# CPU.net
KiCad netlist of a schematic drawn in Altium Designer
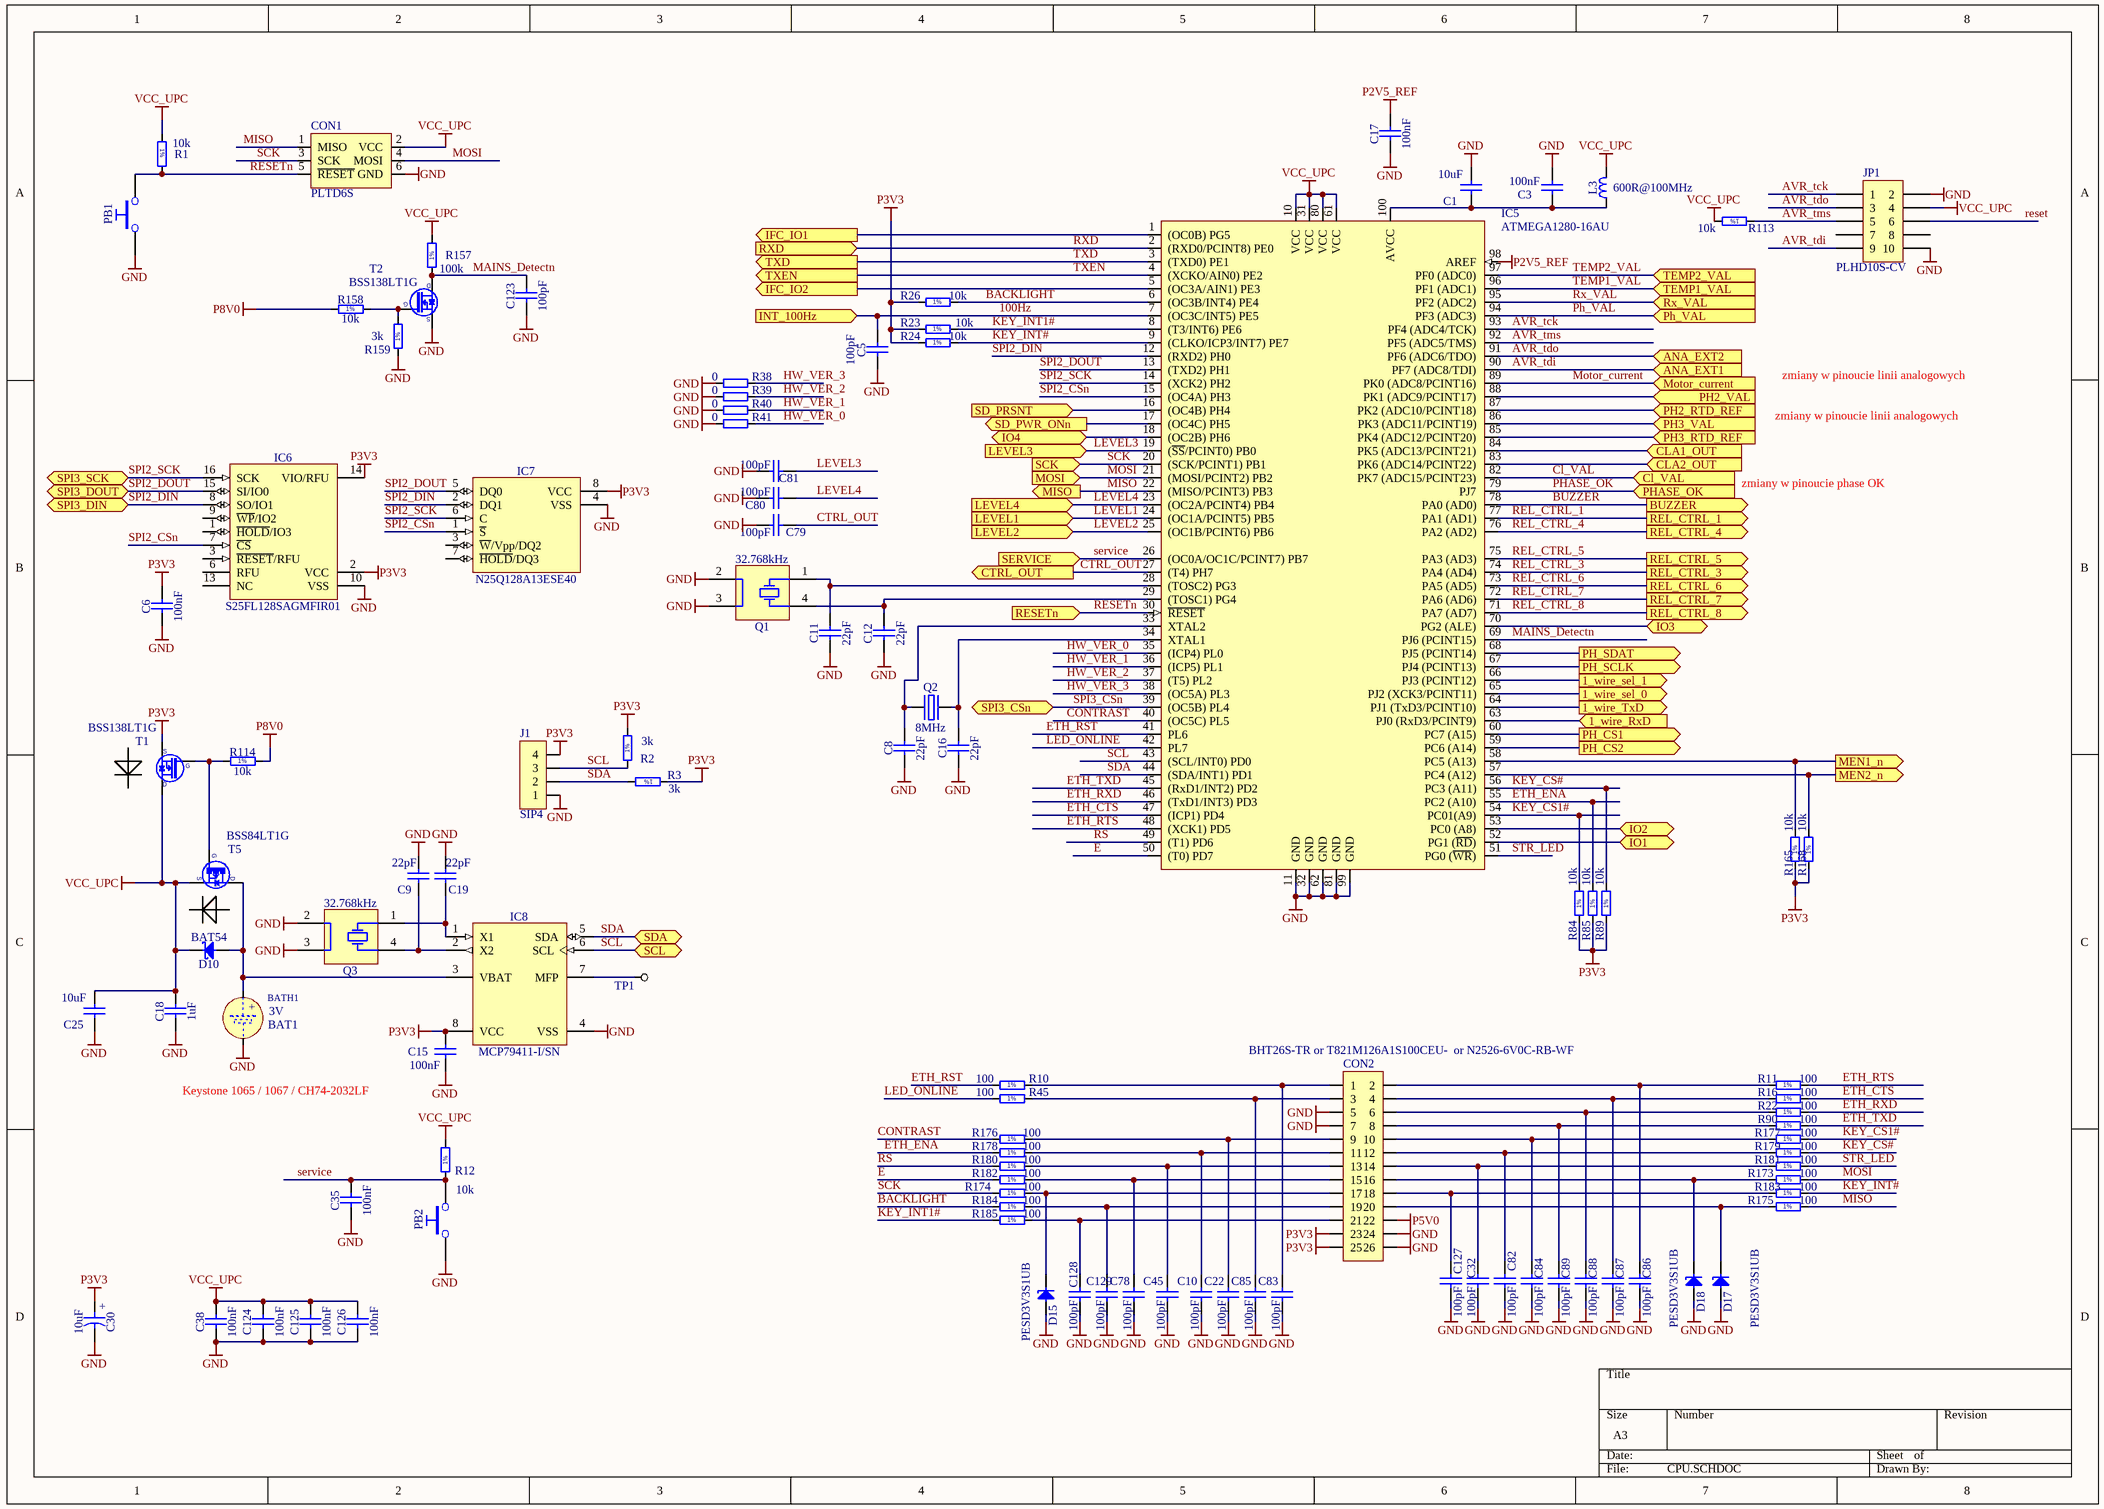
[diagram p0: CPU.SCHDOC]

(export (version "E")
  (design (tool "Eeschema 10.0.6"))
  (components
    (comp (ref "BAT1")
      (value "3V")
      (footprint "BAT_VARTA_CR2032")
      (description "Battery for use only with Socket Holder")
      (fields
        (field (name "PART NUMBER") "BAT_VARTA_CR2032")
        (field (name "POWER") "230mAh")
        (field (name "AUTHOR") "CERN DEM JLC")
      )
      (libsource (lib "Eletro-mechanical") (part "Battery No Pin"))
    )
    (comp (ref "BATH1")
      (value "~")
      (footprint "BATH_KEYSTONE_1065_rev")
      (description "Battery Holder whit 2 Pin")
      (fields
        (field (name "PART NUMBER") "BATH_KEYSTONE_1065")
        (field (name "MANUFACTURER") "KEYSTONE")
        (field (name "AUTHOR") "CERN DEM MR")
      )
      (libsource (lib "LIBRARY_SCH") (part "BATTERY_HOLD_2012"))
    )
    (comp (ref "C1")
      (value "10uF")
      (footprint "CAPC2012X135N")
      (description "Non-polarised capacitor")
      (fields
        (field (name "PART NUMBER") "CC0805_10UF_16V_10%_X5R")
        (field (name "VOLTAGE") "16V")
        (field (name "AUTHOR") "CERN DEM JLC")
      )
      (libsource (lib "Capacitors") (part "Capacitor - non polarized"))
    )
    (comp (ref "C3")
      (value "100nF")
      (footprint "CAPC1608X87N")
      (description "Non-polarised capacitor")
      (fields
        (field (name "PART NUMBER") "CC0603_100NF_50V_10%_X7R")
        (field (name "VOLTAGE") "50V")
        (field (name "AUTHOR") "CERN DEM JLC")
      )
      (libsource (lib "Capacitors") (part "Capacitor - non polarized"))
    )
    (comp (ref "C5")
      (value "100pF")
      (footprint "CAPC1608X87N")
      (description "Non-polarised capacitor")
      (fields
        (field (name "PART NUMBER") "CC0603_100PF_50V_10%_X7R")
        (field (name "VOLTAGE") "50V")
        (field (name "AUTHOR") "CERN DEM JLC")
      )
      (libsource (lib "Capacitors") (part "Capacitor - non polarized"))
    )
    (comp (ref "C6")
      (value "100nF")
      (footprint "CAPC1608X87N")
      (description "Non-polarised capacitor")
      (fields
        (field (name "PART NUMBER") "CC0603_100NF_50V_10%_X7R")
        (field (name "VOLTAGE") "50V")
        (field (name "AUTHOR") "CERN DEM JLC")
      )
      (libsource (lib "Capacitors") (part "Capacitor - non polarized"))
    )
    (comp (ref "C8")
      (value "22pF")
      (footprint "CAPC1608X87N")
      (description "Non-polarised capacitor")
      (fields
        (field (name "PART NUMBER") "CC0603_22PF_50V_5%_NP0")
        (field (name "VOLTAGE") "50V")
        (field (name "AUTHOR") "CERN DEM JLC")
      )
      (libsource (lib "Capacitors") (part "Capacitor - non polarized"))
    )
    (comp (ref "C9")
      (value "22pF")
      (footprint "CAPC1608X87N")
      (description "Non-polarised capacitor")
      (fields
        (field (name "PART NUMBER") "CC0603_22PF_50V_5%_NP0")
        (field (name "VOLTAGE") "50V")
        (field (name "AUTHOR") "CERN DEM JLC")
      )
      (libsource (lib "Capacitors") (part "Capacitor - non polarized"))
    )
    (comp (ref "C10")
      (value "100pF")
      (footprint "CAPC1608X87N")
      (description "Non-polarised capacitor")
      (fields
        (field (name "PART NUMBER") "CC0603_100PF_50V_10%_X7R")
        (field (name "VOLTAGE") "50V")
        (field (name "AUTHOR") "CERN DEM JLC")
      )
      (libsource (lib "Capacitors") (part "Capacitor - non polarized"))
    )
    (comp (ref "C11")
      (value "22pF")
      (footprint "CAPC1608X87N")
      (description "Non-polarised capacitor")
      (fields
        (field (name "PART NUMBER") "CC0603_22PF_50V_5%_NP0")
        (field (name "VOLTAGE") "50V")
        (field (name "AUTHOR") "CERN DEM JLC")
      )
      (libsource (lib "Capacitors") (part "Capacitor - non polarized"))
    )
    (comp (ref "C12")
      (value "22pF")
      (footprint "CAPC1608X87N")
      (description "Non-polarised capacitor")
      (fields
        (field (name "PART NUMBER") "CC0603_22PF_50V_5%_NP0")
        (field (name "VOLTAGE") "50V")
        (field (name "AUTHOR") "CERN DEM JLC")
      )
      (libsource (lib "Capacitors") (part "Capacitor - non polarized"))
    )
    (comp (ref "C15")
      (value "100nF")
      (footprint "CAPC1608X87N")
      (description "Non-polarised capacitor")
      (fields
        (field (name "PART NUMBER") "CC0603_100NF_50V_10%_X7R")
        (field (name "VOLTAGE") "50V")
        (field (name "AUTHOR") "CERN DEM JLC")
      )
      (libsource (lib "Capacitors") (part "Capacitor - non polarized"))
    )
    (comp (ref "C16")
      (value "22pF")
      (footprint "CAPC1608X87N")
      (description "Non-polarised capacitor")
      (fields
        (field (name "PART NUMBER") "CC0603_22PF_50V_5%_NP0")
        (field (name "VOLTAGE") "50V")
        (field (name "AUTHOR") "CERN DEM JLC")
      )
      (libsource (lib "Capacitors") (part "Capacitor - non polarized"))
    )
    (comp (ref "C17")
      (value "100nF")
      (footprint "CAPC1608X87N")
      (description "Non-polarised capacitor")
      (fields
        (field (name "PART NUMBER") "CC0603_100NF_50V_10%_X7R")
        (field (name "VOLTAGE") "50V")
        (field (name "AUTHOR") "CERN DEM JLC")
      )
      (libsource (lib "Capacitors") (part "Capacitor - non polarized"))
    )
    (comp (ref "C18")
      (value "1uF")
      (footprint "CAPC1608X87N")
      (description "Non-polarised capacitor")
      (fields
        (field (name "PART NUMBER") "CC0603_1UF_25V_10%_X7R")
        (field (name "VOLTAGE") "25V")
        (field (name "AUTHOR") "CERN DEM JLC")
      )
      (libsource (lib "Capacitors") (part "Capacitor - non polarized"))
    )
    (comp (ref "C19")
      (value "22pF")
      (footprint "CAPC1608X87N")
      (description "Non-polarised capacitor")
      (fields
        (field (name "PART NUMBER") "CC0603_22PF_50V_5%_NP0")
        (field (name "VOLTAGE") "50V")
        (field (name "AUTHOR") "CERN DEM JLC")
      )
      (libsource (lib "Capacitors") (part "Capacitor - non polarized"))
    )
    (comp (ref "C22")
      (value "100pF")
      (footprint "CAPC1608X87N")
      (description "Non-polarised capacitor")
      (fields
        (field (name "PART NUMBER") "CC0603_100PF_50V_10%_X7R")
        (field (name "VOLTAGE") "50V")
        (field (name "AUTHOR") "CERN DEM JLC")
      )
      (libsource (lib "Capacitors") (part "Capacitor - non polarized"))
    )
    (comp (ref "C25")
      (value "10uF")
      (footprint "CAPC2012X135N")
      (description "Non-polarised capacitor")
      (fields
        (field (name "PART NUMBER") "CC0805_10UF_16V_10%_X5R")
        (field (name "VOLTAGE") "16V")
        (field (name "AUTHOR") "CERN DEM JLC")
      )
      (libsource (lib "Capacitors") (part "Capacitor - non polarized"))
    )
    (comp (ref "C30")
      (value "10uF")
      (footprint "CAPAE430X540N")
      (description "Polarised capacitor")
      (fields
        (field (name "PART NUMBER") "CAE430-540_10UF_25V_20%")
        (field (name "VOLTAGE") "25V")
        (field (name "AUTHOR") "CERN DEM JLC")
      )
      (libsource (lib "Capacitors") (part "Capacitor - polarized"))
    )
    (comp (ref "C32")
      (value "100pF")
      (footprint "CAPC1608X87N")
      (description "Non-polarised capacitor")
      (fields
        (field (name "PART NUMBER") "CC0603_100PF_50V_10%_X7R")
        (field (name "VOLTAGE") "50V")
        (field (name "AUTHOR") "CERN DEM JLC")
      )
      (libsource (lib "Capacitors") (part "Capacitor - non polarized"))
    )
    (comp (ref "C35")
      (value "100nF")
      (footprint "CAPC1608X87N")
      (description "Non-polarised capacitor")
      (fields
        (field (name "PART NUMBER") "CC0603_100NF_50V_10%_X7R")
        (field (name "VOLTAGE") "50V")
        (field (name "AUTHOR") "CERN DEM JLC")
      )
      (libsource (lib "Capacitors") (part "Capacitor - non polarized"))
    )
    (comp (ref "C38")
      (value "100nF")
      (footprint "CAPC1608X87N")
      (description "Non-polarised capacitor")
      (fields
        (field (name "PART NUMBER") "CC0603_100NF_50V_10%_X7R")
        (field (name "VOLTAGE") "50V")
        (field (name "AUTHOR") "CERN DEM JLC")
      )
      (libsource (lib "Capacitors") (part "Capacitor - non polarized"))
    )
    (comp (ref "C45")
      (value "100pF")
      (footprint "CAPC1608X87N")
      (description "Non-polarised capacitor")
      (fields
        (field (name "PART NUMBER") "CC0603_100PF_50V_10%_X7R")
        (field (name "VOLTAGE") "50V")
        (field (name "AUTHOR") "CERN DEM JLC")
      )
      (libsource (lib "Capacitors") (part "Capacitor - non polarized"))
    )
    (comp (ref "C78")
      (value "100pF")
      (footprint "CAPC1608X87N")
      (description "Non-polarised capacitor")
      (fields
        (field (name "PART NUMBER") "CC0603_100PF_50V_10%_X7R")
        (field (name "VOLTAGE") "50V")
        (field (name "AUTHOR") "CERN DEM JLC")
      )
      (libsource (lib "Capacitors") (part "Capacitor - non polarized"))
    )
    (comp (ref "C79")
      (value "100pF")
      (footprint "CAPC1608X87N")
      (description "Non-polarised capacitor")
      (fields
        (field (name "PART NUMBER") "CC0603_100PF_50V_10%_X7R")
        (field (name "VOLTAGE") "50V")
        (field (name "AUTHOR") "CERN DEM JLC")
      )
      (libsource (lib "Capacitors") (part "Capacitor - non polarized"))
    )
    (comp (ref "C80")
      (value "100pF")
      (footprint "CAPC1608X87N")
      (description "Non-polarised capacitor")
      (fields
        (field (name "PART NUMBER") "CC0603_100PF_50V_10%_X7R")
        (field (name "VOLTAGE") "50V")
        (field (name "AUTHOR") "CERN DEM JLC")
      )
      (libsource (lib "Capacitors") (part "Capacitor - non polarized"))
    )
    (comp (ref "C81")
      (value "100pF")
      (footprint "CAPC1608X87N")
      (description "Non-polarised capacitor")
      (fields
        (field (name "PART NUMBER") "CC0603_100PF_50V_10%_X7R")
        (field (name "VOLTAGE") "50V")
        (field (name "AUTHOR") "CERN DEM JLC")
      )
      (libsource (lib "Capacitors") (part "Capacitor - non polarized"))
    )
    (comp (ref "C82")
      (value "100pF")
      (footprint "CAPC1608X87N")
      (description "Non-polarised capacitor")
      (fields
        (field (name "PART NUMBER") "CC0603_100PF_50V_10%_X7R")
        (field (name "VOLTAGE") "50V")
        (field (name "AUTHOR") "CERN DEM JLC")
      )
      (libsource (lib "Capacitors") (part "Capacitor - non polarized"))
    )
    (comp (ref "C83")
      (value "100pF")
      (footprint "CAPC1608X87N")
      (description "Non-polarised capacitor")
      (fields
        (field (name "PART NUMBER") "CC0603_100PF_50V_10%_X7R")
        (field (name "VOLTAGE") "50V")
        (field (name "AUTHOR") "CERN DEM JLC")
      )
      (libsource (lib "Capacitors") (part "Capacitor - non polarized"))
    )
    (comp (ref "C84")
      (value "100pF")
      (footprint "CAPC1608X87N")
      (description "Non-polarised capacitor")
      (fields
        (field (name "PART NUMBER") "CC0603_100PF_50V_10%_X7R")
        (field (name "VOLTAGE") "50V")
        (field (name "AUTHOR") "CERN DEM JLC")
      )
      (libsource (lib "Capacitors") (part "Capacitor - non polarized"))
    )
    (comp (ref "C85")
      (value "100pF")
      (footprint "CAPC1608X87N")
      (description "Non-polarised capacitor")
      (fields
        (field (name "PART NUMBER") "CC0603_100PF_50V_10%_X7R")
        (field (name "VOLTAGE") "50V")
        (field (name "AUTHOR") "CERN DEM JLC")
      )
      (libsource (lib "Capacitors") (part "Capacitor - non polarized"))
    )
    (comp (ref "C86")
      (value "100pF")
      (footprint "CAPC1608X87N")
      (description "Non-polarised capacitor")
      (fields
        (field (name "PART NUMBER") "CC0603_100PF_50V_10%_X7R")
        (field (name "VOLTAGE") "50V")
        (field (name "AUTHOR") "CERN DEM JLC")
      )
      (libsource (lib "Capacitors") (part "Capacitor - non polarized"))
    )
    (comp (ref "C87")
      (value "100pF")
      (footprint "CAPC1608X87N")
      (description "Non-polarised capacitor")
      (fields
        (field (name "PART NUMBER") "CC0603_100PF_50V_10%_X7R")
        (field (name "VOLTAGE") "50V")
        (field (name "AUTHOR") "CERN DEM JLC")
      )
      (libsource (lib "Capacitors") (part "Capacitor - non polarized"))
    )
    (comp (ref "C88")
      (value "100pF")
      (footprint "CAPC1608X87N")
      (description "Non-polarised capacitor")
      (fields
        (field (name "PART NUMBER") "CC0603_100PF_50V_10%_X7R")
        (field (name "VOLTAGE") "50V")
        (field (name "AUTHOR") "CERN DEM JLC")
      )
      (libsource (lib "Capacitors") (part "Capacitor - non polarized"))
    )
    (comp (ref "C89")
      (value "100pF")
      (footprint "CAPC1608X87N")
      (description "Non-polarised capacitor")
      (fields
        (field (name "PART NUMBER") "CC0603_100PF_50V_10%_X7R")
        (field (name "VOLTAGE") "50V")
        (field (name "AUTHOR") "CERN DEM JLC")
      )
      (libsource (lib "Capacitors") (part "Capacitor - non polarized"))
    )
    (comp (ref "C123")
      (value "100pF")
      (footprint "CAPC1608X87N")
      (description "Non-polarised capacitor")
      (fields
        (field (name "PART NUMBER") "CC0603_100PF_50V_10%_X7R")
        (field (name "VOLTAGE") "50V")
        (field (name "AUTHOR") "CERN DEM JLC")
      )
      (libsource (lib "Capacitors") (part "Capacitor - non polarized"))
    )
    (comp (ref "C124")
      (value "100nF")
      (footprint "CAPC1608X87N")
      (description "Non-polarised capacitor")
      (fields
        (field (name "PART NUMBER") "CC0603_100NF_50V_10%_X7R")
        (field (name "VOLTAGE") "50V")
        (field (name "AUTHOR") "CERN DEM JLC")
      )
      (libsource (lib "Capacitors") (part "Capacitor - non polarized"))
    )
    (comp (ref "C125")
      (value "100nF")
      (footprint "CAPC1608X87N")
      (description "Non-polarised capacitor")
      (fields
        (field (name "PART NUMBER") "CC0603_100NF_50V_10%_X7R")
        (field (name "VOLTAGE") "50V")
        (field (name "AUTHOR") "CERN DEM JLC")
      )
      (libsource (lib "Capacitors") (part "Capacitor - non polarized"))
    )
    (comp (ref "C126")
      (value "100nF")
      (footprint "CAPC1608X87N")
      (description "Non-polarised capacitor")
      (fields
        (field (name "PART NUMBER") "CC0603_100NF_50V_10%_X7R")
        (field (name "VOLTAGE") "50V")
        (field (name "AUTHOR") "CERN DEM JLC")
      )
      (libsource (lib "Capacitors") (part "Capacitor - non polarized"))
    )
    (comp (ref "C127")
      (value "100pF")
      (footprint "CAPC1608X87N")
      (description "Non-polarised capacitor")
      (fields
        (field (name "PART NUMBER") "CC0603_100PF_50V_10%_X7R")
        (field (name "VOLTAGE") "50V")
        (field (name "AUTHOR") "CERN DEM JLC")
      )
      (libsource (lib "Capacitors") (part "Capacitor - non polarized"))
    )
    (comp (ref "C128")
      (value "100pF")
      (footprint "CAPC1608X87N")
      (description "Non-polarised capacitor")
      (fields
        (field (name "PART NUMBER") "CC0603_100PF_50V_10%_X7R")
        (field (name "VOLTAGE") "50V")
        (field (name "AUTHOR") "CERN DEM JLC")
      )
      (libsource (lib "Capacitors") (part "Capacitor - non polarized"))
    )
    (comp (ref "C129")
      (value "100pF")
      (footprint "CAPC1608X87N")
      (description "Non-polarised capacitor")
      (fields
        (field (name "PART NUMBER") "CC0603_100PF_50V_10%_X7R")
        (field (name "VOLTAGE") "50V")
        (field (name "AUTHOR") "CERN DEM JLC")
      )
      (libsource (lib "Capacitors") (part "Capacitor - non polarized"))
    )
    (comp (ref "CON1")
      (value "PLTD6S")
      (footprint "PLTD6S")
      (description "6x 2.54mm SMT  dual row pin header")
      (libsource (lib "LIBRARY_SCH") (part "CON_ISP"))
    )
    (comp (ref "CON2")
      (value "BHT26S-TR or T821M126A1S100CEU-  or N2526-6V0C-RB-WF")
      (footprint "BHT26S")
      (description "Maritex BHT 26S, 3M N2526-6V0C-RB-WF, Amphenol T821M126A1S100CEU")
      (libsource (lib "LIBRARY_SCH") (part "CON_IDC26_SMT"))
    )
    (comp (ref "D10")
      (value "BAT54")
      (footprint "SOT95P240X130-3N")
      (description "Diode Schottky  Anode Pin 1 Cathode Pin 3 (Pas de pin 2)")
      (fields
        (field (name "VOLTAGE") "30V")
        (field (name "POWER") "200mA")
        (field (name "AUTHOR") "CERN DEM JLC")
      )
      (libsource (lib "ICs And Semiconductors") (part "Diode Schottky A1C3"))
    )
    (comp (ref "D15")
      (value "PESD3V3S1UB")
      (footprint "SODFL1608X65N")
      (description "ESD protection diode")
      (fields
        (field (name "VOLTAGE") "3V3")
        (field (name "POWER") "330W")
        (field (name "AUTHOR") "CERN DEM JLC")
      )
      (libsource (lib "ICs And Semiconductors") (part "Diode ESD"))
    )
    (comp (ref "D17")
      (value "PESD3V3S1UB")
      (footprint "SODFL1608X65N")
      (description "ESD protection diode")
      (fields
        (field (name "VOLTAGE") "3V3")
        (field (name "POWER") "330W")
        (field (name "AUTHOR") "CERN DEM JLC")
      )
      (libsource (lib "ICs And Semiconductors") (part "Diode ESD"))
    )
    (comp (ref "D18")
      (value "PESD3V3S1UB")
      (footprint "SODFL1608X65N")
      (description "ESD protection diode")
      (fields
        (field (name "VOLTAGE") "3V3")
        (field (name "POWER") "330W")
        (field (name "AUTHOR") "CERN DEM JLC")
      )
      (libsource (lib "ICs And Semiconductors") (part "Diode ESD"))
    )
    (comp (ref "IC5")
      (value "ATMEGA1280-16AU")
      (footprint "TQFP100")
      (description "8MHz, 8 bit AVR microcontroller")
      (libsource (lib "LIBRARY_SCH") (part "UPC_ATMEGA1280"))
    )
    (comp (ref "IC6")
      (value "S25FL128SAGMFIR01")
      (footprint "SOIC127P1030X265-16N")
      (fields (field (name "MANUFACTURER") "SPANSION") (field (name "AUTHOR") "CERN DEM JLC"))
      (libsource (lib "ICs And Semiconductors") (part "S25FL128SAGMFIR01"))
    )
    (comp (ref "IC7")
      (value "N25Q128A13ESE40")
      (footprint "SOIC127P790X216-8N")
      (description "128Mb, 3V, Multiple I/O Serial NOR Flash Memory")
      (fields (field (name "MANUFACTURER") "MICRON TECHNOLOGY") (field (name "AUTHOR") "CERN DEM JLC"))
      (libsource (lib "ICs And Semiconductors") (part "N25Q128A13ESE40"))
    )
    (comp (ref "IC8")
      (value "MCP79411-I/SN")
      (footprint "SOIC127P600X175-8N")
      (description "I2C Real-Time Clock/Calendar with EEPROM, SRAM, Unique ID and Battery Switchover")
      (fields (field (name "MANUFACTURER") "MICROCHIP TECHNOLOGY") (field (name "AUTHOR") "GK"))
      (libsource (lib "LIBRARY_SCH") (part "RTC_MCP79411"))
    )
    (comp (ref "J1")
      (value "SIP4")
      (footprint "SIP4")
      (description "Connector")
      (libsource (lib "LIBRARY_SCH") (part "CON4"))
    )
    (comp (ref "JP1")
      (value "PLHD10S-CV")
      (footprint "CON_2x5_MINI")
      (description "Goldpin 1.27mm")
      (libsource (lib "LIBRARY_SCH") (part "CON_2x5 1.27 male"))
    )
    (comp (ref "L3")
      (value "600R@100MHz")
      (footprint "INDC1608X95N")
      (description "Inductor")
      (fields
        (field (name "PART NUMBER") "IND0603_MURATA_BLM18BD601SN1D")
        (field (name "POWER") "200mA")
        (field (name "AUTHOR") "CERN DEM JLC")
      )
      (libsource (lib "Inductors & Transformers") (part "Inductor"))
    )
    (comp (ref "PB1")
      (value "Push Button")
      (footprint "PB_TYCO_FSMSM")
      (description "Push-Button Switch SPDT")
      (fields
        (field (name "PART NUMBER") "PB_TYCO_FSMSM")
        (field (name "MANUFACTURER") "TYCO ELECTRONICS")
        (field (name "AUTHOR") "CERN DEM JLC")
      )
      (libsource (lib "Eletro-mechanical") (part "PB SPST 1NO-2NO"))
    )
    (comp (ref "PB2")
      (value "Push Button")
      (footprint "PB_TYCO_FSMSM")
      (description "Push-Button Switch SPDT")
      (fields
        (field (name "PART NUMBER") "PB_TYCO_FSMSM")
        (field (name "MANUFACTURER") "TYCO ELECTRONICS")
        (field (name "AUTHOR") "CERN DEM JLC")
      )
      (libsource (lib "Eletro-mechanical") (part "PB SPST 1NO-2NO"))
    )
    (comp (ref "Q1")
      (value "32.768kHz")
      (footprint "XTAL_ABRACON_ABS25")
      (description "Crystal 4 pins 1=XTAL Control 2 And 3=NC 4=XTAL")
      (fields
        (field (name "PART NUMBER") "XTAL_32.768KHZ_ABRACON_ABS25-32.768KHZ-T")
        (field (name "MANUFACTURER") "ABRACON")
        (field (name "AUTHOR") "CERN DEM JMW")
      )
      (libsource (lib "ICs And Semiconductors") (part "Quartz Crystal 1X 2-3NC 4X"))
    )
    (comp (ref "Q2")
      (value "8MHz")
      (footprint "XTAL_TXC_7A")
      (description "Quartz Crystal")
      (fields
        (field (name "PART NUMBER") "XTAL_8MHZ_TXC_7A-8.000MAAE-T")
        (field (name "MANUFACTURER") "TXC CORPORATION")
        (field (name "AUTHOR") "CERN DEM JLC")
      )
      (libsource (lib "ICs And Semiconductors") (part "Quartz Crystal"))
    )
    (comp (ref "Q3")
      (value "32.768kHz")
      (footprint "XTAL_ABRACON_ABS25")
      (description "Crystal 4 pins 1=XTAL Control 2 And 3=NC 4=XTAL")
      (fields
        (field (name "PART NUMBER") "XTAL_32.768KHZ_ABRACON_ABS25-32.768KHZ-T")
        (field (name "MANUFACTURER") "ABRACON")
        (field (name "AUTHOR") "CERN DEM JMW")
      )
      (libsource (lib "ICs And Semiconductors") (part "Quartz Crystal 1X 2-3NC 4X"))
    )
    (comp (ref "R1")
      (value "10k")
      (footprint "RESC1608X55N")
      (description "Resistor - 1%")
      (fields
        (field (name "PART NUMBER") "R0603_10K_1%_0.1W_100PPM")
        (field (name "POWER") "0.1W")
        (field (name "AUTHOR") "CERN DEM JLC")
      )
      (libsource (lib "Resistors") (part "Resistor - 1%"))
    )
    (comp (ref "R2")
      (value "3k")
      (footprint "RESC1608X55N")
      (description "Resistor - 1%")
      (fields
        (field (name "PART NUMBER") "R0603_3K_1%_0.1W_100PPM")
        (field (name "POWER") "0.1W")
        (field (name "AUTHOR") "CERN DEM JLC")
      )
      (libsource (lib "Resistors") (part "Resistor - 1%"))
    )
    (comp (ref "R3")
      (value "3k")
      (footprint "RESC1608X55N")
      (description "Resistor - 1%")
      (fields
        (field (name "PART NUMBER") "R0603_3K_1%_0.1W_100PPM")
        (field (name "POWER") "0.1W")
        (field (name "AUTHOR") "CERN DEM JLC")
      )
      (libsource (lib "Resistors") (part "Resistor - 1%"))
    )
    (comp (ref "R10")
      (value "100")
      (footprint "RESC1608X55N")
      (description "Resistor - 1%")
      (fields
        (field (name "PART NUMBER") "R0603_100R_1%_0.1W_100PPM")
        (field (name "POWER") "0.1W")
        (field (name "AUTHOR") "CERN DEM JLC")
      )
      (libsource (lib "Resistors") (part "Resistor - 1%"))
    )
    (comp (ref "R11")
      (value "100")
      (footprint "RESC1608X55N")
      (description "Resistor - 1%")
      (fields
        (field (name "PART NUMBER") "R0603_100R_1%_0.1W_100PPM")
        (field (name "POWER") "0.1W")
        (field (name "AUTHOR") "CERN DEM JLC")
      )
      (libsource (lib "Resistors") (part "Resistor - 1%"))
    )
    (comp (ref "R12")
      (value "10k")
      (footprint "RESC1608X55N")
      (description "Resistor - 1%")
      (fields
        (field (name "PART NUMBER") "R0603_10K_1%_0.1W_100PPM")
        (field (name "POWER") "0.1W")
        (field (name "AUTHOR") "CERN DEM JLC")
      )
      (libsource (lib "Resistors") (part "Resistor - 1%"))
    )
    (comp (ref "R16")
      (value "100")
      (footprint "RESC1608X55N")
      (description "Resistor - 1%")
      (fields
        (field (name "PART NUMBER") "R0603_100R_1%_0.1W_100PPM")
        (field (name "POWER") "0.1W")
        (field (name "AUTHOR") "CERN DEM JLC")
      )
      (libsource (lib "Resistors") (part "Resistor - 1%"))
    )
    (comp (ref "R22")
      (value "100")
      (footprint "RESC1608X55N")
      (description "Resistor - 1%")
      (fields
        (field (name "PART NUMBER") "R0603_100R_1%_0.1W_100PPM")
        (field (name "POWER") "0.1W")
        (field (name "AUTHOR") "CERN DEM JLC")
      )
      (libsource (lib "Resistors") (part "Resistor - 1%"))
    )
    (comp (ref "R23")
      (value "10k")
      (footprint "RESC1608X55N")
      (description "Resistor - 1%")
      (fields
        (field (name "PART NUMBER") "R0603_10K_1%_0.1W_100PPM")
        (field (name "POWER") "0.1W")
        (field (name "AUTHOR") "CERN DEM JLC")
      )
      (libsource (lib "Resistors") (part "Resistor - 1%"))
    )
    (comp (ref "R24")
      (value "10k")
      (footprint "RESC1608X55N")
      (description "Resistor - 1%")
      (fields
        (field (name "PART NUMBER") "R0603_10K_1%_0.1W_100PPM")
        (field (name "POWER") "0.1W")
        (field (name "AUTHOR") "CERN DEM JLC")
      )
      (libsource (lib "Resistors") (part "Resistor - 1%"))
    )
    (comp (ref "R26")
      (value "10k")
      (footprint "RESC1608X55N")
      (description "Resistor - 1%")
      (fields
        (field (name "PART NUMBER") "R0603_10K_1%_0.1W_100PPM")
        (field (name "POWER") "0.1W")
        (field (name "AUTHOR") "CERN DEM JLC")
      )
      (libsource (lib "Resistors") (part "Resistor - 1%"))
    )
    (comp (ref "R38")
      (value "0")
      (footprint "RESC1608X55N")
      (description "Resistor")
      (fields
        (field (name "PART NUMBER") "R0603_0R_JUMPER")
        (field (name "MANUFACTURER") "GENERIC")
        (field (name "AUTHOR") "CERN DEM JLC")
      )
      (libsource (lib "Resistors") (part "Resistor"))
    )
    (comp (ref "R39")
      (value "0")
      (footprint "RESC1608X55N")
      (description "Resistor")
      (fields
        (field (name "PART NUMBER") "R0603_0R_JUMPER")
        (field (name "MANUFACTURER") "GENERIC")
        (field (name "AUTHOR") "CERN DEM JLC")
      )
      (libsource (lib "Resistors") (part "Resistor"))
    )
    (comp (ref "R40")
      (value "0")
      (footprint "RESC1608X55N")
      (description "Resistor")
      (fields
        (field (name "PART NUMBER") "R0603_0R_JUMPER")
        (field (name "MANUFACTURER") "GENERIC")
        (field (name "AUTHOR") "CERN DEM JLC")
      )
      (libsource (lib "Resistors") (part "Resistor"))
    )
    (comp (ref "R41")
      (value "0")
      (footprint "RESC1608X55N")
      (description "Resistor")
      (fields
        (field (name "PART NUMBER") "R0603_0R_JUMPER")
        (field (name "MANUFACTURER") "GENERIC")
        (field (name "AUTHOR") "CERN DEM JLC")
      )
      (libsource (lib "Resistors") (part "Resistor"))
    )
    (comp (ref "R45")
      (value "100")
      (footprint "RESC1608X55N")
      (description "Resistor - 1%")
      (fields
        (field (name "PART NUMBER") "R0603_100R_1%_0.1W_100PPM")
        (field (name "POWER") "0.1W")
        (field (name "AUTHOR") "CERN DEM JLC")
      )
      (libsource (lib "Resistors") (part "Resistor - 1%"))
    )
    (comp (ref "R84")
      (value "10k")
      (footprint "RESC1608X55N")
      (description "Resistor - 1%")
      (fields
        (field (name "PART NUMBER") "R0603_10K_1%_0.1W_100PPM")
        (field (name "POWER") "0.1W")
        (field (name "AUTHOR") "CERN DEM JLC")
      )
      (libsource (lib "Resistors") (part "Resistor - 1%"))
    )
    (comp (ref "R85")
      (value "10k")
      (footprint "RESC1608X55N")
      (description "Resistor - 1%")
      (fields
        (field (name "PART NUMBER") "R0603_10K_1%_0.1W_100PPM")
        (field (name "POWER") "0.1W")
        (field (name "AUTHOR") "CERN DEM JLC")
      )
      (libsource (lib "Resistors") (part "Resistor - 1%"))
    )
    (comp (ref "R89")
      (value "10k")
      (footprint "RESC1608X55N")
      (description "Resistor - 1%")
      (fields
        (field (name "PART NUMBER") "R0603_10K_1%_0.1W_100PPM")
        (field (name "POWER") "0.1W")
        (field (name "AUTHOR") "CERN DEM JLC")
      )
      (libsource (lib "Resistors") (part "Resistor - 1%"))
    )
    (comp (ref "R90")
      (value "100")
      (footprint "RESC1608X55N")
      (description "Resistor - 1%")
      (fields
        (field (name "PART NUMBER") "R0603_100R_1%_0.1W_100PPM")
        (field (name "POWER") "0.1W")
        (field (name "AUTHOR") "CERN DEM JLC")
      )
      (libsource (lib "Resistors") (part "Resistor - 1%"))
    )
    (comp (ref "R113")
      (value "10k")
      (footprint "RESC1608X55N")
      (description "Resistor - 1%")
      (fields
        (field (name "PART NUMBER") "R0603_10K_1%_0.1W_100PPM")
        (field (name "POWER") "0.1W")
        (field (name "AUTHOR") "CERN DEM JLC")
      )
      (libsource (lib "Resistors") (part "Resistor - 1%"))
    )
    (comp (ref "R114")
      (value "10k")
      (footprint "RESC1608X55N")
      (description "Resistor - 1%")
      (fields
        (field (name "PART NUMBER") "R0603_10K_1%_0.1W_100PPM")
        (field (name "POWER") "0.1W")
        (field (name "AUTHOR") "CERN DEM JLC")
      )
      (libsource (lib "Resistors") (part "Resistor - 1%"))
    )
    (comp (ref "R157")
      (value "100k")
      (footprint "RESC1608X55N")
      (description "Resistor - 1%")
      (fields
        (field (name "PART NUMBER") "R0603_100K_1%_0.1W_100PPM")
        (field (name "POWER") "0.1W")
        (field (name "AUTHOR") "CERN DEM JLC")
      )
      (libsource (lib "Resistors") (part "Resistor - 1%"))
    )
    (comp (ref "R158")
      (value "10k")
      (footprint "RESC1608X55N")
      (description "Resistor - 1%")
      (fields
        (field (name "PART NUMBER") "R0603_10K_1%_0.1W_100PPM")
        (field (name "POWER") "0.1W")
        (field (name "AUTHOR") "CERN DEM JLC")
      )
      (libsource (lib "Resistors") (part "Resistor - 1%"))
    )
    (comp (ref "R159")
      (value "3k")
      (footprint "RESC1608X55N")
      (description "Resistor - 1%")
      (fields
        (field (name "PART NUMBER") "R0603_3K_1%_0.1W_100PPM")
        (field (name "POWER") "0.1W")
        (field (name "AUTHOR") "CERN DEM JLC")
      )
      (libsource (lib "Resistors") (part "Resistor - 1%"))
    )
    (comp (ref "R165")
      (value "10k")
      (footprint "RESC1608X55N")
      (description "Resistor - 1%")
      (fields
        (field (name "PART NUMBER") "R0603_10K_1%_0.1W_100PPM")
        (field (name "POWER") "0.1W")
        (field (name "AUTHOR") "CERN DEM JLC")
      )
      (libsource (lib "Resistors") (part "Resistor - 1%"))
    )
    (comp (ref "R168")
      (value "10k")
      (footprint "RESC1608X55N")
      (description "Resistor - 1%")
      (fields
        (field (name "PART NUMBER") "R0603_10K_1%_0.1W_100PPM")
        (field (name "POWER") "0.1W")
        (field (name "AUTHOR") "CERN DEM JLC")
      )
      (libsource (lib "Resistors") (part "Resistor - 1%"))
    )
    (comp (ref "R173")
      (value "100")
      (footprint "RESC1608X55N")
      (description "Resistor - 1%")
      (fields
        (field (name "PART NUMBER") "R0603_100R_1%_0.1W_100PPM")
        (field (name "POWER") "0.1W")
        (field (name "AUTHOR") "CERN DEM JLC")
      )
      (libsource (lib "Resistors") (part "Resistor - 1%"))
    )
    (comp (ref "R174")
      (value "100")
      (footprint "RESC1608X55N")
      (description "Resistor - 1%")
      (fields
        (field (name "PART NUMBER") "R0603_100R_1%_0.1W_100PPM")
        (field (name "POWER") "0.1W")
        (field (name "AUTHOR") "CERN DEM JLC")
      )
      (libsource (lib "Resistors") (part "Resistor - 1%"))
    )
    (comp (ref "R175")
      (value "100")
      (footprint "RESC1608X55N")
      (description "Resistor - 1%")
      (fields
        (field (name "PART NUMBER") "R0603_100R_1%_0.1W_100PPM")
        (field (name "POWER") "0.1W")
        (field (name "AUTHOR") "CERN DEM JLC")
      )
      (libsource (lib "Resistors") (part "Resistor - 1%"))
    )
    (comp (ref "R176")
      (value "100")
      (footprint "RESC1608X55N")
      (description "Resistor - 1%")
      (fields
        (field (name "PART NUMBER") "R0603_100R_1%_0.1W_100PPM")
        (field (name "POWER") "0.1W")
        (field (name "AUTHOR") "CERN DEM JLC")
      )
      (libsource (lib "Resistors") (part "Resistor - 1%"))
    )
    (comp (ref "R177")
      (value "100")
      (footprint "RESC1608X55N")
      (description "Resistor - 1%")
      (fields
        (field (name "PART NUMBER") "R0603_100R_1%_0.1W_100PPM")
        (field (name "POWER") "0.1W")
        (field (name "AUTHOR") "CERN DEM JLC")
      )
      (libsource (lib "Resistors") (part "Resistor - 1%"))
    )
    (comp (ref "R178")
      (value "100")
      (footprint "RESC1608X55N")
      (description "Resistor - 1%")
      (fields
        (field (name "PART NUMBER") "R0603_100R_1%_0.1W_100PPM")
        (field (name "POWER") "0.1W")
        (field (name "AUTHOR") "CERN DEM JLC")
      )
      (libsource (lib "Resistors") (part "Resistor - 1%"))
    )
    (comp (ref "R179")
      (value "100")
      (footprint "RESC1608X55N")
      (description "Resistor - 1%")
      (fields
        (field (name "PART NUMBER") "R0603_100R_1%_0.1W_100PPM")
        (field (name "POWER") "0.1W")
        (field (name "AUTHOR") "CERN DEM JLC")
      )
      (libsource (lib "Resistors") (part "Resistor - 1%"))
    )
    (comp (ref "R180")
      (value "100")
      (footprint "RESC1608X55N")
      (description "Resistor - 1%")
      (fields
        (field (name "PART NUMBER") "R0603_100R_1%_0.1W_100PPM")
        (field (name "POWER") "0.1W")
        (field (name "AUTHOR") "CERN DEM JLC")
      )
      (libsource (lib "Resistors") (part "Resistor - 1%"))
    )
    (comp (ref "R181")
      (value "100")
      (footprint "RESC1608X55N")
      (description "Resistor - 1%")
      (fields
        (field (name "PART NUMBER") "R0603_100R_1%_0.1W_100PPM")
        (field (name "POWER") "0.1W")
        (field (name "AUTHOR") "CERN DEM JLC")
      )
      (libsource (lib "Resistors") (part "Resistor - 1%"))
    )
    (comp (ref "R182")
      (value "100")
      (footprint "RESC1608X55N")
      (description "Resistor - 1%")
      (fields
        (field (name "PART NUMBER") "R0603_100R_1%_0.1W_100PPM")
        (field (name "POWER") "0.1W")
        (field (name "AUTHOR") "CERN DEM JLC")
      )
      (libsource (lib "Resistors") (part "Resistor - 1%"))
    )
    (comp (ref "R183")
      (value "100")
      (footprint "RESC1608X55N")
      (description "Resistor - 1%")
      (fields
        (field (name "PART NUMBER") "R0603_100R_1%_0.1W_100PPM")
        (field (name "POWER") "0.1W")
        (field (name "AUTHOR") "CERN DEM JLC")
      )
      (libsource (lib "Resistors") (part "Resistor - 1%"))
    )
    (comp (ref "R184")
      (value "100")
      (footprint "RESC1608X55N")
      (description "Resistor - 1%")
      (fields
        (field (name "PART NUMBER") "R0603_100R_1%_0.1W_100PPM")
        (field (name "POWER") "0.1W")
        (field (name "AUTHOR") "CERN DEM JLC")
      )
      (libsource (lib "Resistors") (part "Resistor - 1%"))
    )
    (comp (ref "R185")
      (value "100")
      (footprint "RESC1608X55N")
      (description "Resistor - 1%")
      (fields
        (field (name "PART NUMBER") "R0603_100R_1%_0.1W_100PPM")
        (field (name "POWER") "0.1W")
        (field (name "AUTHOR") "CERN DEM JLC")
      )
      (libsource (lib "Resistors") (part "Resistor - 1%"))
    )
    (comp (ref "T1")
      (value "BSS138LT1G")
      (footprint "SOT95P240X110-3N")
      (description "N-CHANNEL MOSFET WITH DIODE")
      (fields (field (name "MANUFACTURER") "ON SEMICONDUCTOR") (field (name "AUTHOR") "CERN DEM JLC"))
      (libsource (lib "") (part "N-MOSFET-D 1G 2S 3D_1"))
    )
    (comp (ref "T2")
      (value "BSS138LT1G")
      (footprint "SOT95P240X110-3N")
      (description "N-CHANNEL MOSFET WITH DIODE")
      (fields (field (name "MANUFACTURER") "ON SEMICONDUCTOR") (field (name "AUTHOR") "CERN DEM JLC"))
      (libsource (lib "ICs And Semiconductors") (part "N-MOSFET-D 1G 2S 3D"))
    )
    (comp (ref "T5")
      (value "BSS84LT1G")
      (footprint "SOT95P240X110-3N")
      (description "P-CHANNEL MOSFET WITH DIODE")
      (fields (field (name "MANUFACTURER") "ON SEMICONDUCTOR") (field (name "AUTHOR") "CERN DEM JLC"))
      (libsource (lib "ICs And Semiconductors") (part "P-MOSFET-D 1G 2S 3D"))
    )
    (comp (ref "TP1")
      (value "TP")
      (footprint "TP")
      (description "Testpoint")
      (libsource (lib "*") (part "TP"))
    )
  )
  (nets
    (net (code "1") (name "/1_wire_RxD") (class "Default")
      (node (ref "IC5") (pin "63") (pinfunction "PJ0_(RxD3/PCINT9)_63") (pintype "bidirectional"))
    )
    (net (code "2") (name "/1_wire_TxD") (class "Default")
      (node (ref "IC5") (pin "64") (pinfunction "PJ1_(TxD3/PCINT10)_64") (pintype "bidirectional"))
    )
    (net (code "3") (name "/1_wire_sel_0") (class "Default")
      (node (ref "IC5") (pin "65") (pinfunction "PJ2_(XCK3/PCINT11)_65") (pintype "bidirectional"))
    )
    (net (code "4") (name "/1_wire_sel_1") (class "Default")
      (node (ref "IC5") (pin "66") (pinfunction "PJ3_(PCINT12)_66") (pintype "bidirectional"))
    )
    (net (code "5") (name "/100Hz") (class "Default")
      (node (ref "C5") (pin "2") (pinfunction "2_2") (pintype "passive"))
      (node (ref "IC5") (pin "7") (pinfunction "(OC3C/INT5)_PE5_7") (pintype "bidirectional"))
    )
    (net (code "6") (name "/AVR_tck") (class "Default")
      (node (ref "IC5") (pin "93") (pinfunction "PF4_(ADC4/TCK)_93") (pintype "bidirectional"))
      (node (ref "JP1") (pin "1") (pinfunction "1_1") (pintype "passive"))
    )
    (net (code "7") (name "/AVR_tdi") (class "Default")
      (node (ref "IC5") (pin "90") (pinfunction "PF7_(ADC8/TDI)_90") (pintype "bidirectional"))
      (node (ref "JP1") (pin "9") (pinfunction "9_9") (pintype "passive"))
    )
    (net (code "8") (name "/AVR_tdo") (class "Default")
      (node (ref "IC5") (pin "91") (pinfunction "PF6_(ADC6/TDO)_91") (pintype "bidirectional"))
      (node (ref "JP1") (pin "3") (pinfunction "3_3") (pintype "passive"))
    )
    (net (code "9") (name "/AVR_tms") (class "Default")
      (node (ref "IC5") (pin "92") (pinfunction "PF5_(ADC5/TMS)_92") (pintype "bidirectional"))
      (node (ref "JP1") (pin "5") (pinfunction "5_5") (pintype "passive"))
      (node (ref "R113") (pin "1") (pinfunction "1_1") (pintype "passive"))
    )
    (net (code "10") (name "/BACKLIGHT") (class "Default")
      (node (ref "IC5") (pin "6") (pinfunction "(OC3B/INT4)_PE4_6") (pintype "bidirectional"))
      (node (ref "R184") (pin "1") (pinfunction "1_1") (pintype "passive"))
      (node (ref "R26") (pin "2") (pinfunction "2_2") (pintype "passive"))
    )
    (net (code "11") (name "/BUZZER") (class "Default")
      (node (ref "IC5") (pin "78") (pinfunction "PA0_(AD0)_78") (pintype "bidirectional"))
    )
    (net (code "12") (name "/CLA1_OUT") (class "Default")
      (node (ref "IC5") (pin "84") (pinfunction "PK5_(ADC13/PCINT21)_84") (pintype "bidirectional"))
    )
    (net (code "13") (name "/CLA2_OUT") (class "Default")
      (node (ref "IC5") (pin "83") (pinfunction "PK6_(ADC14/PCINT22)_83") (pintype "bidirectional"))
    )
    (net (code "14") (name "/CONTRAST") (class "Default")
      (node (ref "IC5") (pin "40") (pinfunction "(OC5C)_PL5_40") (pintype "bidirectional"))
      (node (ref "R176") (pin "1") (pinfunction "1_1") (pintype "passive"))
    )
    (net (code "15") (name "/CTRL_OUT") (class "Default")
      (node (ref "C79") (pin "2") (pinfunction "2_2") (pintype "passive"))
      (node (ref "IC5") (pin "27") (pinfunction "(T4)_PH7_27") (pintype "bidirectional"))
    )
    (net (code "16") (name "/Cl_VAL") (class "Default")
      (node (ref "IC5") (pin "82") (pinfunction "PK7_(ADC15/PCINT23)_82") (pintype "bidirectional"))
    )
    (net (code "17") (name "/E") (class "Default")
      (node (ref "IC5") (pin "50") (pinfunction "(T0)_PD7_50") (pintype "bidirectional"))
      (node (ref "R182") (pin "1") (pinfunction "1_1") (pintype "passive"))
    )
    (net (code "18") (name "/ETH_CTS") (class "Default")
      (node (ref "IC5") (pin "47") (pinfunction "(ICP1)_PD4_47") (pintype "bidirectional"))
      (node (ref "R16") (pin "2") (pinfunction "2_2") (pintype "passive"))
    )
    (net (code "19") (name "/ETH_ENA") (class "Default")
      (node (ref "IC5") (pin "55") (pinfunction "PC2_(A10)_55") (pintype "bidirectional"))
      (node (ref "R178") (pin "1") (pinfunction "1_1") (pintype "passive"))
      (node (ref "R85") (pin "2") (pinfunction "2_2") (pintype "passive"))
    )
    (net (code "20") (name "/ETH_RST") (class "Default")
      (node (ref "IC5") (pin "41") (pinfunction "PL6_41") (pintype "bidirectional"))
      (node (ref "R10") (pin "1") (pinfunction "1_1") (pintype "passive"))
    )
    (net (code "21") (name "/ETH_RTS") (class "Default")
      (node (ref "IC5") (pin "48") (pinfunction "(XCK1)_PD5_48") (pintype "bidirectional"))
      (node (ref "R11") (pin "2") (pinfunction "2_2") (pintype "passive"))
    )
    (net (code "22") (name "/ETH_RXD") (class "Default")
      (node (ref "IC5") (pin "46") (pinfunction "(TxD1/INT3)_PD3_46") (pintype "bidirectional"))
      (node (ref "R22") (pin "2") (pinfunction "2_2") (pintype "passive"))
    )
    (net (code "23") (name "/ETH_TXD") (class "Default")
      (node (ref "IC5") (pin "45") (pinfunction "(RxD1/INT2)_PD2_45") (pintype "bidirectional"))
      (node (ref "R90") (pin "2") (pinfunction "2_2") (pintype "passive"))
    )
    (net (code "24") (name "/HW_VER_0") (class "Default")
      (node (ref "IC5") (pin "35") (pinfunction "(ICP4)_PL0_35") (pintype "bidirectional"))
      (node (ref "R41") (pin "2") (pinfunction "2_2") (pintype "passive"))
    )
    (net (code "25") (name "/HW_VER_1") (class "Default")
      (node (ref "IC5") (pin "36") (pinfunction "(ICP5)_PL1_36") (pintype "bidirectional"))
      (node (ref "R40") (pin "2") (pinfunction "2_2") (pintype "passive"))
    )
    (net (code "26") (name "/HW_VER_2") (class "Default")
      (node (ref "IC5") (pin "37") (pinfunction "(T5)_PL2_37") (pintype "bidirectional"))
      (node (ref "R39") (pin "2") (pinfunction "2_2") (pintype "passive"))
    )
    (net (code "27") (name "/HW_VER_3") (class "Default")
      (node (ref "IC5") (pin "38") (pinfunction "(OC5A)_PL3_38") (pintype "bidirectional"))
      (node (ref "R38") (pin "2") (pinfunction "2_2") (pintype "passive"))
    )
    (net (code "28") (name "/IFC_IO1") (class "Default")
      (node (ref "IC5") (pin "1") (pinfunction "(OC0B)_PG5_1") (pintype "bidirectional"))
    )
    (net (code "29") (name "/IFC_IO2") (class "Default")
      (node (ref "IC5") (pin "5") (pinfunction "(OC3A/AIN1)_PE3_5") (pintype "bidirectional"))
    )
    (net (code "30") (name "/IO1") (class "Default")
      (node (ref "IC5") (pin "52") (pinfunction "PG1_(~{RD})_52") (pintype "bidirectional"))
    )
    (net (code "31") (name "/IO2") (class "Default")
      (node (ref "IC5") (pin "53") (pinfunction "PC0_(A8)_53") (pintype "bidirectional"))
    )
    (net (code "32") (name "/IO3") (class "Default")
      (node (ref "IC5") (pin "70") (pinfunction "PG2_(ALE)_70") (pintype "bidirectional"))
    )
    (net (code "33") (name "/IO4") (class "Default")
      (node (ref "IC5") (pin "18") (pinfunction "(OC2B)_PH6_18") (pintype "bidirectional"))
    )
    (net (code "34") (name "/KEY_CS#") (class "Default")
      (node (ref "IC5") (pin "56") (pinfunction "PC3_(A11)_56") (pintype "bidirectional"))
      (node (ref "R179") (pin "2") (pinfunction "2_2") (pintype "passive"))
      (node (ref "R89") (pin "2") (pinfunction "2_2") (pintype "passive"))
    )
    (net (code "35") (name "/KEY_CS1#") (class "Default")
      (node (ref "IC5") (pin "54") (pinfunction "PC01(A9)_54") (pintype "bidirectional"))
      (node (ref "R177") (pin "2") (pinfunction "2_2") (pintype "passive"))
      (node (ref "R84") (pin "2") (pinfunction "2_2") (pintype "passive"))
    )
    (net (code "36") (name "/KEY_INT#") (class "Default")
      (node (ref "IC5") (pin "9") (pinfunction "(CLKO/ICP3/INT7)_PE7_9") (pintype "bidirectional"))
      (node (ref "R183") (pin "2") (pinfunction "2_2") (pintype "passive"))
      (node (ref "R24") (pin "2") (pinfunction "2_2") (pintype "passive"))
    )
    (net (code "37") (name "/KEY_INT1#") (class "Default")
      (node (ref "IC5") (pin "8") (pinfunction "(T3/INT6)_PE6_8") (pintype "bidirectional"))
      (node (ref "R185") (pin "1") (pinfunction "1_1") (pintype "passive"))
      (node (ref "R23") (pin "2") (pinfunction "2_2") (pintype "passive"))
    )
    (net (code "38") (name "/LED_ONLINE") (class "Default")
      (node (ref "IC5") (pin "42") (pinfunction "PL7_42") (pintype "bidirectional"))
      (node (ref "R45") (pin "1") (pinfunction "1_1") (pintype "passive"))
    )
    (net (code "39") (name "/LEVEL1") (class "Default")
      (node (ref "IC5") (pin "24") (pinfunction "(OC1A/PCINT5)_PB5_24") (pintype "bidirectional"))
    )
    (net (code "40") (name "/LEVEL2") (class "Default")
      (node (ref "IC5") (pin "25") (pinfunction "(OC1B/PCINT6)_PB6_25") (pintype "bidirectional"))
    )
    (net (code "41") (name "/LEVEL3") (class "Default")
      (node (ref "C81") (pin "2") (pinfunction "2_2") (pintype "passive"))
      (node (ref "IC5") (pin "19") (pinfunction "(~{SS}/PCINT0)_PB0_19") (pintype "bidirectional"))
    )
    (net (code "42") (name "/LEVEL4") (class "Default")
      (node (ref "C80") (pin "2") (pinfunction "2_2") (pintype "passive"))
      (node (ref "IC5") (pin "23") (pinfunction "(OC2A/PCINT4)_PB4_23") (pintype "bidirectional"))
    )
    (net (code "43") (name "/MAINS_Detectn") (class "Default")
      (node (ref "C123") (pin "2") (pinfunction "2_2") (pintype "passive"))
      (node (ref "IC5") (pin "69") (pinfunction "PJ6_(PCINT15)_69") (pintype "bidirectional"))
      (node (ref "R157") (pin "1") (pinfunction "1_1") (pintype "passive"))
      (node (ref "T2") (pin "3") (pinfunction "D_3") (pintype "passive"))
    )
    (net (code "44") (name "/MEN1_n") (class "Default")
      (node (ref "IC5") (pin "58") (pinfunction "PC5_(A13)_58") (pintype "bidirectional"))
      (node (ref "R165") (pin "2") (pinfunction "2_2") (pintype "passive"))
    )
    (net (code "45") (name "/MEN2_n") (class "Default")
      (node (ref "IC5") (pin "57") (pinfunction "PC4_(A12)_57") (pintype "bidirectional"))
      (node (ref "R168") (pin "2") (pinfunction "2_2") (pintype "passive"))
    )
    (net (code "46") (name "/MISO") (class "Default")
      (node (ref "CON1") (pin "1") (pinfunction "MISO_1") (pintype "passive"))
      (node (ref "IC5") (pin "22") (pinfunction "(MISO/PCINT3)_PB3_22") (pintype "bidirectional"))
      (node (ref "R175") (pin "2") (pinfunction "2_2") (pintype "passive"))
    )
    (net (code "47") (name "/MOSI") (class "Default")
      (node (ref "CON1") (pin "4") (pinfunction "MOSI_4") (pintype "passive"))
      (node (ref "IC5") (pin "21") (pinfunction "(MOSI/PCINT2)_PB2_21") (pintype "bidirectional"))
      (node (ref "R173") (pin "2") (pinfunction "2_2") (pintype "passive"))
    )
    (net (code "48") (name "/Motor_current") (class "Default")
      (node (ref "IC5") (pin "89") (pinfunction "PK0_(ADC8/PCINT16)_89") (pintype "bidirectional"))
    )
    (net (code "49") (name "/PH2_RTD_REF") (class "Default")
      (node (ref "IC5") (pin "87") (pinfunction "PK2_(ADC10/PCINT18)_87") (pintype "bidirectional"))
    )
    (net (code "50") (name "/PH2_VAL") (class "Default")
      (node (ref "IC5") (pin "88") (pinfunction "PK1_(ADC9/PCINT17)_88") (pintype "bidirectional"))
    )
    (net (code "51") (name "/PH3_RTD_REF") (class "Default")
      (node (ref "IC5") (pin "85") (pinfunction "PK4_(ADC12/PCINT20)_85") (pintype "bidirectional"))
    )
    (net (code "52") (name "/PH3_VAL") (class "Default")
      (node (ref "IC5") (pin "86") (pinfunction "PK3_(ADC11/PCINT19)_86") (pintype "bidirectional"))
    )
    (net (code "53") (name "/PHASE_OK") (class "Default")
      (node (ref "IC5") (pin "79") (pinfunction "PJ7_79") (pintype "bidirectional"))
    )
    (net (code "54") (name "/PH_CS1") (class "Default")
      (node (ref "IC5") (pin "60") (pinfunction "PC7_(A15)_60") (pintype "bidirectional"))
    )
    (net (code "55") (name "/PH_CS2") (class "Default")
      (node (ref "IC5") (pin "59") (pinfunction "PC6_(A14)_59") (pintype "bidirectional"))
    )
    (net (code "56") (name "/PH_SCLK") (class "Default")
      (node (ref "IC5") (pin "67") (pinfunction "PJ4_(PCINT13)_67") (pintype "bidirectional"))
    )
    (net (code "57") (name "/PH_SDAT") (class "Default")
      (node (ref "IC5") (pin "68") (pinfunction "PJ5_(PCINT14)_68") (pintype "bidirectional"))
    )
    (net (code "58") (name "/Ph_VAL") (class "Default")
      (node (ref "IC5") (pin "94") (pinfunction "PF3_(ADC3)_94") (pintype "bidirectional"))
    )
    (net (code "59") (name "/REL_CTRL_1") (class "Default")
      (node (ref "IC5") (pin "77") (pinfunction "PA1_(AD1)_77") (pintype "bidirectional"))
    )
    (net (code "60") (name "/REL_CTRL_3") (class "Default")
      (node (ref "IC5") (pin "74") (pinfunction "PA4_(AD4)_74") (pintype "bidirectional"))
    )
    (net (code "61") (name "/REL_CTRL_4") (class "Default")
      (node (ref "IC5") (pin "76") (pinfunction "PA2_(AD2)_76") (pintype "bidirectional"))
    )
    (net (code "62") (name "/REL_CTRL_5") (class "Default")
      (node (ref "IC5") (pin "75") (pinfunction "PA3_(AD3)_75") (pintype "bidirectional"))
    )
    (net (code "63") (name "/REL_CTRL_6") (class "Default")
      (node (ref "IC5") (pin "73") (pinfunction "PA5_(AD5)_73") (pintype "bidirectional"))
    )
    (net (code "64") (name "/REL_CTRL_7") (class "Default")
      (node (ref "IC5") (pin "72") (pinfunction "PA6_(AD6)_72") (pintype "bidirectional"))
    )
    (net (code "65") (name "/REL_CTRL_8") (class "Default")
      (node (ref "IC5") (pin "71") (pinfunction "PA7_(AD7)_71") (pintype "bidirectional"))
    )
    (net (code "66") (name "/RESETn") (class "Default")
      (node (ref "CON1") (pin "5") (pinfunction "~{RESET}_5") (pintype "passive"))
      (node (ref "IC5") (pin "30") (pinfunction "~{RESET}_30") (pintype "input"))
      (node (ref "PB1") (pin "2") (pinfunction "2_2") (pintype "passive"))
      (node (ref "R1") (pin "2") (pinfunction "2_2") (pintype "passive"))
    )
    (net (code "67") (name "/RS") (class "Default")
      (node (ref "IC5") (pin "49") (pinfunction "(T1)_PD6_49") (pintype "bidirectional"))
      (node (ref "R180") (pin "1") (pinfunction "1_1") (pintype "passive"))
    )
    (net (code "68") (name "/RXD") (class "Default")
      (node (ref "IC5") (pin "2") (pinfunction "(RXD0/PCINT8)_PE0_2") (pintype "bidirectional"))
    )
    (net (code "69") (name "/Rx_VAL") (class "Default")
      (node (ref "IC5") (pin "95") (pinfunction "PF2_(ADC2)_95") (pintype "bidirectional"))
    )
    (net (code "70") (name "/SCK") (class "Default")
      (node (ref "CON1") (pin "3") (pinfunction "SCK_3") (pintype "passive"))
      (node (ref "IC5") (pin "20") (pinfunction "(SCK/PCINT1)_PB1_20") (pintype "bidirectional"))
      (node (ref "R174") (pin "1") (pinfunction "1_1") (pintype "passive"))
    )
    (net (code "71") (name "/SCL") (class "Default")
      (node (ref "IC5") (pin "43") (pinfunction "(SCL/INT0)_PD0_43") (pintype "bidirectional"))
      (node (ref "IC8") (pin "6") (pinfunction "SCL_6") (pintype "input"))
      (node (ref "J1") (pin "3") (pinfunction "3_3") (pintype "passive"))
      (node (ref "R2") (pin "1") (pinfunction "1_1") (pintype "passive"))
    )
    (net (code "72") (name "/SDA") (class "Default")
      (node (ref "IC5") (pin "44") (pinfunction "(SDA/INT1)_PD1_44") (pintype "bidirectional"))
      (node (ref "IC8") (pin "5") (pinfunction "SDA_5") (pintype "bidirectional"))
      (node (ref "J1") (pin "2") (pinfunction "2_2") (pintype "passive"))
      (node (ref "R3") (pin "2") (pinfunction "2_2") (pintype "passive"))
    )
    (net (code "73") (name "/SD_PRSNT") (class "Default")
      (node (ref "IC5") (pin "16") (pinfunction "(OC4B)_PH4_16") (pintype "bidirectional"))
    )
    (net (code "74") (name "/SD_PWR_ONn") (class "Default")
      (node (ref "IC5") (pin "17") (pinfunction "(OC4C)_PH5_17") (pintype "bidirectional"))
    )
    (net (code "75") (name "/SPI2_CSn") (class "Default")
      (node (ref "IC5") (pin "15") (pinfunction "(OC4A)_PH3_15") (pintype "bidirectional"))
      (node (ref "IC6") (pin "7") (pinfunction "~{CS}_7") (pintype "input"))
      (node (ref "IC7") (pin "1") (pinfunction "~{S}_1") (pintype "input"))
    )
    (net (code "76") (name "/SPI2_DIN") (class "Default")
      (node (ref "IC5") (pin "12") (pinfunction "(RXD2)_PH0_12") (pintype "bidirectional"))
      (node (ref "IC6") (pin "8") (pinfunction "SO/IO1_8") (pintype "bidirectional"))
      (node (ref "IC7") (pin "2") (pinfunction "DQ1_2") (pintype "bidirectional"))
    )
    (net (code "77") (name "/SPI2_DOUT") (class "Default")
      (node (ref "IC5") (pin "13") (pinfunction "(TXD2)_PH1_13") (pintype "bidirectional"))
      (node (ref "IC6") (pin "15") (pinfunction "SI/IO0_15") (pintype "bidirectional"))
      (node (ref "IC7") (pin "5") (pinfunction "DQ0_5") (pintype "bidirectional"))
    )
    (net (code "78") (name "/SPI2_SCK") (class "Default")
      (node (ref "IC5") (pin "14") (pinfunction "(XCK2)_PH2_14") (pintype "bidirectional"))
      (node (ref "IC6") (pin "16") (pinfunction "SCK_16") (pintype "input"))
      (node (ref "IC7") (pin "6") (pinfunction "C_6") (pintype "input"))
    )
    (net (code "79") (name "/SPI3_CSn") (class "Default")
      (node (ref "IC5") (pin "39") (pinfunction "(OC5B)_PL4_39") (pintype "bidirectional"))
    )
    (net (code "80") (name "/STR_LED") (class "Default")
      (node (ref "IC5") (pin "51") (pinfunction "PG0_(~{WR})_51") (pintype "bidirectional"))
      (node (ref "R181") (pin "2") (pinfunction "2_2") (pintype "passive"))
    )
    (net (code "81") (name "/TEMP1_VAL") (class "Default")
      (node (ref "IC5") (pin "96") (pinfunction "PF1_(ADC1)_96") (pintype "bidirectional"))
    )
    (net (code "82") (name "/TEMP2_VAL") (class "Default")
      (node (ref "IC5") (pin "97") (pinfunction "PF0_(ADC0)_97") (pintype "power_in"))
    )
    (net (code "83") (name "/TXD") (class "Default")
      (node (ref "IC5") (pin "3") (pinfunction "(TXD0)_PE1_3") (pintype "bidirectional"))
    )
    (net (code "84") (name "/TXEN") (class "Default")
      (node (ref "IC5") (pin "4") (pinfunction "(XCKO/AIN0)_PE2_4") (pintype "bidirectional"))
    )
    (net (code "85") (name "/reset") (class "Default")
      (node (ref "JP1") (pin "6") (pinfunction "6_6") (pintype "passive"))
    )
    (net (code "86") (name "/service") (class "Default")
      (node (ref "C35") (pin "2") (pinfunction "2_2") (pintype "passive"))
      (node (ref "IC5") (pin "26") (pinfunction "(OC0A/OC1C/PCINT7)_PB7_26") (pintype "bidirectional"))
      (node (ref "PB2") (pin "2") (pinfunction "2_2") (pintype "passive"))
      (node (ref "R12") (pin "1") (pinfunction "1_1") (pintype "passive"))
    )
    (net (code "87") (name "GND") (class "Default")
      (node (ref "BATH1") (pin "2") (pinfunction "MINUS_2") (pintype "power_in"))
      (node (ref "C1") (pin "2") (pinfunction "2_2") (pintype "passive"))
      (node (ref "C10") (pin "2") (pinfunction "2_2") (pintype "passive"))
      (node (ref "C11") (pin "1") (pinfunction "1_1") (pintype "passive"))
      (node (ref "C12") (pin "1") (pinfunction "1_1") (pintype "passive"))
      (node (ref "C123") (pin "1") (pinfunction "1_1") (pintype "passive"))
      (node (ref "C124") (pin "1") (pinfunction "1_1") (pintype "passive"))
      (node (ref "C125") (pin "1") (pinfunction "1_1") (pintype "passive"))
      (node (ref "C126") (pin "1") (pinfunction "1_1") (pintype "passive"))
      (node (ref "C127") (pin "1") (pinfunction "1_1") (pintype "passive"))
      (node (ref "C128") (pin "1") (pinfunction "1_1") (pintype "passive"))
      (node (ref "C129") (pin "1") (pinfunction "1_1") (pintype "passive"))
      (node (ref "C15") (pin "2") (pinfunction "2_2") (pintype "passive"))
      (node (ref "C16") (pin "1") (pinfunction "1_1") (pintype "passive"))
      (node (ref "C17") (pin "1") (pinfunction "1_1") (pintype "passive"))
      (node (ref "C18") (pin "1") (pinfunction "1_1") (pintype "passive"))
      (node (ref "C19") (pin "2") (pinfunction "2_2") (pintype "passive"))
      (node (ref "C22") (pin "2") (pinfunction "2_2") (pintype "passive"))
      (node (ref "C25") (pin "1") (pinfunction "1_1") (pintype "passive"))
      (node (ref "C3") (pin "2") (pinfunction "2_2") (pintype "passive"))
      (node (ref "C30") (pin "2") (pinfunction "2_2") (pintype "passive"))
      (node (ref "C32") (pin "1") (pinfunction "1_1") (pintype "passive"))
      (node (ref "C35") (pin "1") (pinfunction "1_1") (pintype "passive"))
      (node (ref "C38") (pin "1") (pinfunction "1_1") (pintype "passive"))
      (node (ref "C45") (pin "1") (pinfunction "1_1") (pintype "passive"))
      (node (ref "C5") (pin "1") (pinfunction "1_1") (pintype "passive"))
      (node (ref "C6") (pin "1") (pinfunction "1_1") (pintype "passive"))
      (node (ref "C78") (pin "1") (pinfunction "1_1") (pintype "passive"))
      (node (ref "C79") (pin "1") (pinfunction "1_1") (pintype "passive"))
      (node (ref "C8") (pin "1") (pinfunction "1_1") (pintype "passive"))
      (node (ref "C80") (pin "1") (pinfunction "1_1") (pintype "passive"))
      (node (ref "C81") (pin "1") (pinfunction "1_1") (pintype "passive"))
      (node (ref "C82") (pin "1") (pinfunction "1_1") (pintype "passive"))
      (node (ref "C83") (pin "1") (pinfunction "1_1") (pintype "passive"))
      (node (ref "C84") (pin "1") (pinfunction "1_1") (pintype "passive"))
      (node (ref "C85") (pin "1") (pinfunction "1_1") (pintype "passive"))
      (node (ref "C86") (pin "1") (pinfunction "1_1") (pintype "passive"))
      (node (ref "C87") (pin "1") (pinfunction "1_1") (pintype "passive"))
      (node (ref "C88") (pin "1") (pinfunction "1_1") (pintype "passive"))
      (node (ref "C89") (pin "1") (pinfunction "1_1") (pintype "passive"))
      (node (ref "C9") (pin "2") (pinfunction "2_2") (pintype "passive"))
      (node (ref "CON1") (pin "6") (pinfunction "GND_6") (pintype "passive"))
      (node (ref "CON2") (pin "24") (pinfunction "24_24") (pintype "passive"))
      (node (ref "CON2") (pin "26") (pinfunction "26_26") (pintype "passive"))
      (node (ref "CON2") (pin "5") (pinfunction "5_5") (pintype "passive"))
      (node (ref "CON2") (pin "7") (pinfunction "7_7") (pintype "passive"))
      (node (ref "D15") (pin "2") (pinfunction "A_2") (pintype "passive"))
      (node (ref "D17") (pin "2") (pinfunction "A_2") (pintype "passive"))
      (node (ref "D18") (pin "2") (pinfunction "A_2") (pintype "passive"))
      (node (ref "IC5") (pin "11") (pinfunction "GND_11") (pintype "power_in"))
      (node (ref "IC5") (pin "32") (pinfunction "GND_32") (pintype "power_in"))
      (node (ref "IC5") (pin "62") (pinfunction "GND_62") (pintype "power_in"))
      (node (ref "IC5") (pin "81") (pinfunction "GND_81") (pintype "power_in"))
      (node (ref "IC5") (pin "99") (pinfunction "GND_99") (pintype "power_in"))
      (node (ref "IC6") (pin "10") (pinfunction "VSS_10") (pintype "power_in"))
      (node (ref "IC7") (pin "4") (pinfunction "VSS_4") (pintype "power_in"))
      (node (ref "IC8") (pin "4") (pinfunction "VSS_4") (pintype "power_in"))
      (node (ref "J1") (pin "1") (pinfunction "1_1") (pintype "passive"))
      (node (ref "JP1") (pin "10") (pinfunction "10_10") (pintype "passive"))
      (node (ref "JP1") (pin "2") (pinfunction "2_2") (pintype "passive"))
      (node (ref "PB1") (pin "1") (pinfunction "1_1") (pintype "passive"))
      (node (ref "PB2") (pin "1") (pinfunction "1_1") (pintype "passive"))
      (node (ref "Q1") (pin "2") (pinfunction "GND_2") (pintype "power_in"))
      (node (ref "Q1") (pin "3") (pinfunction "GND_3") (pintype "power_in"))
      (node (ref "Q3") (pin "2") (pinfunction "GND_2") (pintype "power_in"))
      (node (ref "Q3") (pin "3") (pinfunction "GND_3") (pintype "power_in"))
      (node (ref "R159") (pin "1") (pinfunction "1_1") (pintype "passive"))
      (node (ref "R38") (pin "1") (pinfunction "1_1") (pintype "passive"))
      (node (ref "R39") (pin "1") (pinfunction "1_1") (pintype "passive"))
      (node (ref "R40") (pin "1") (pinfunction "1_1") (pintype "passive"))
      (node (ref "R41") (pin "1") (pinfunction "1_1") (pintype "passive"))
      (node (ref "T2") (pin "2") (pinfunction "S_2") (pintype "passive"))
    )
    (net (code "88") (name "Net-(BATH1-PLUS)") (class "Default")
      (node (ref "BATH1") (pin "1") (pinfunction "PLUS_1") (pintype "power_in"))
      (node (ref "D10") (pin "1") (pinfunction "A_1") (pintype "passive"))
      (node (ref "IC8") (pin "3") (pinfunction "VBAT_3") (pintype "power_in"))
      (node (ref "T5") (pin "3") (pinfunction "D_3") (pintype "passive"))
    )
    (net (code "89") (name "Net-(C10-Pad1)") (class "Default")
      (node (ref "C10") (pin "1") (pinfunction "1_1") (pintype "passive"))
      (node (ref "CON2") (pin "11") (pinfunction "11_11") (pintype "passive"))
      (node (ref "R178") (pin "2") (pinfunction "2_2") (pintype "passive"))
    )
    (net (code "90") (name "Net-(C22-Pad1)") (class "Default")
      (node (ref "C22") (pin "1") (pinfunction "1_1") (pintype "passive"))
      (node (ref "CON2") (pin "9") (pinfunction "9_9") (pintype "passive"))
      (node (ref "R176") (pin "2") (pinfunction "2_2") (pintype "passive"))
    )
    (net (code "91") (name "Net-(C32-Pad2)") (class "Default")
      (node (ref "C32") (pin "2") (pinfunction "2_2") (pintype "passive"))
      (node (ref "CON2") (pin "14") (pinfunction "14_14") (pintype "passive"))
      (node (ref "R181") (pin "1") (pinfunction "1_1") (pintype "passive"))
    )
    (net (code "92") (name "Net-(C45-Pad2)") (class "Default")
      (node (ref "C45") (pin "2") (pinfunction "2_2") (pintype "passive"))
      (node (ref "CON2") (pin "13") (pinfunction "13_13") (pintype "passive"))
      (node (ref "R180") (pin "2") (pinfunction "2_2") (pintype "passive"))
    )
    (net (code "93") (name "Net-(C78-Pad2)") (class "Default")
      (node (ref "C78") (pin "2") (pinfunction "2_2") (pintype "passive"))
      (node (ref "CON2") (pin "15") (pinfunction "15_15") (pintype "passive"))
      (node (ref "R182") (pin "2") (pinfunction "2_2") (pintype "passive"))
    )
    (net (code "94") (name "Net-(C82-Pad2)") (class "Default")
      (node (ref "C82") (pin "2") (pinfunction "2_2") (pintype "passive"))
      (node (ref "CON2") (pin "12") (pinfunction "12_12") (pintype "passive"))
      (node (ref "R179") (pin "1") (pinfunction "1_1") (pintype "passive"))
    )
    (net (code "95") (name "Net-(C83-Pad2)") (class "Default")
      (node (ref "C83") (pin "2") (pinfunction "2_2") (pintype "passive"))
      (node (ref "CON2") (pin "1") (pinfunction "1_1") (pintype "passive"))
      (node (ref "R10") (pin "2") (pinfunction "2_2") (pintype "passive"))
    )
    (net (code "96") (name "Net-(C84-Pad2)") (class "Default")
      (node (ref "C84") (pin "2") (pinfunction "2_2") (pintype "passive"))
      (node (ref "CON2") (pin "10") (pinfunction "10_10") (pintype "passive"))
      (node (ref "R177") (pin "1") (pinfunction "1_1") (pintype "passive"))
    )
    (net (code "97") (name "Net-(C85-Pad2)") (class "Default")
      (node (ref "C85") (pin "2") (pinfunction "2_2") (pintype "passive"))
      (node (ref "CON2") (pin "3") (pinfunction "3_3") (pintype "passive"))
      (node (ref "R45") (pin "2") (pinfunction "2_2") (pintype "passive"))
    )
    (net (code "98") (name "Net-(C86-Pad2)") (class "Default")
      (node (ref "C86") (pin "2") (pinfunction "2_2") (pintype "passive"))
      (node (ref "CON2") (pin "2") (pinfunction "2_2") (pintype "passive"))
      (node (ref "R11") (pin "1") (pinfunction "1_1") (pintype "passive"))
    )
    (net (code "99") (name "Net-(C87-Pad2)") (class "Default")
      (node (ref "C87") (pin "2") (pinfunction "2_2") (pintype "passive"))
      (node (ref "CON2") (pin "4") (pinfunction "4_4") (pintype "passive"))
      (node (ref "R16") (pin "1") (pinfunction "1_1") (pintype "passive"))
    )
    (net (code "100") (name "Net-(C88-Pad2)") (class "Default")
      (node (ref "C88") (pin "2") (pinfunction "2_2") (pintype "passive"))
      (node (ref "CON2") (pin "6") (pinfunction "6_6") (pintype "passive"))
      (node (ref "R22") (pin "1") (pinfunction "1_1") (pintype "passive"))
    )
    (net (code "101") (name "Net-(C89-Pad2)") (class "Default")
      (node (ref "C89") (pin "2") (pinfunction "2_2") (pintype "passive"))
      (node (ref "CON2") (pin "8") (pinfunction "8_8") (pintype "passive"))
      (node (ref "R90") (pin "1") (pinfunction "1_1") (pintype "passive"))
    )
    (net (code "102") (name "Net-(C127-Pad2)") (class "Default")
      (node (ref "C127") (pin "2") (pinfunction "2_2") (pintype "passive"))
      (node (ref "CON2") (pin "18") (pinfunction "18_18") (pintype "passive"))
      (node (ref "R183") (pin "1") (pinfunction "1_1") (pintype "passive"))
    )
    (net (code "103") (name "Net-(C128-Pad2)") (class "Default")
      (node (ref "C128") (pin "2") (pinfunction "2_2") (pintype "passive"))
      (node (ref "CON2") (pin "21") (pinfunction "21_21") (pintype "passive"))
      (node (ref "R185") (pin "2") (pinfunction "2_2") (pintype "passive"))
    )
    (net (code "104") (name "Net-(C129-Pad2)") (class "Default")
      (node (ref "C129") (pin "2") (pinfunction "2_2") (pintype "passive"))
      (node (ref "CON2") (pin "19") (pinfunction "19_19") (pintype "passive"))
      (node (ref "R184") (pin "2") (pinfunction "2_2") (pintype "passive"))
    )
    (net (code "105") (name "Net-(D15-C)") (class "Default")
      (node (ref "CON2") (pin "17") (pinfunction "17_17") (pintype "passive"))
      (node (ref "D15") (pin "1") (pinfunction "C_1") (pintype "passive"))
      (node (ref "R174") (pin "2") (pinfunction "2_2") (pintype "passive"))
    )
    (net (code "106") (name "Net-(D17-C)") (class "Default")
      (node (ref "CON2") (pin "20") (pinfunction "20_20") (pintype "passive"))
      (node (ref "D17") (pin "1") (pinfunction "C_1") (pintype "passive"))
      (node (ref "R175") (pin "1") (pinfunction "1_1") (pintype "passive"))
    )
    (net (code "107") (name "Net-(D18-C)") (class "Default")
      (node (ref "CON2") (pin "16") (pinfunction "16_16") (pintype "passive"))
      (node (ref "D18") (pin "1") (pinfunction "C_1") (pintype "passive"))
      (node (ref "R173") (pin "1") (pinfunction "1_1") (pintype "passive"))
    )
    (net (code "108") (name "Net-(IC5-(TOSC1)_PG4)") (class "Default")
      (node (ref "C12") (pin "2") (pinfunction "2_2") (pintype "passive"))
      (node (ref "IC5") (pin "29") (pinfunction "(TOSC1)_PG4_29") (pintype "bidirectional"))
      (node (ref "Q1") (pin "4") (pinfunction "X_4") (pintype "passive"))
    )
    (net (code "109") (name "Net-(IC5-(TOSC2)_PG3)") (class "Default")
      (node (ref "C11") (pin "2") (pinfunction "2_2") (pintype "passive"))
      (node (ref "IC5") (pin "28") (pinfunction "(TOSC2)_PG3_28") (pintype "bidirectional"))
      (node (ref "Q1") (pin "1") (pinfunction "X_1") (pintype "passive"))
    )
    (net (code "110") (name "Net-(IC5-AVCC)") (class "Default")
      (node (ref "C1") (pin "1") (pinfunction "1_1") (pintype "passive"))
      (node (ref "C3") (pin "1") (pinfunction "1_1") (pintype "passive"))
      (node (ref "IC5") (pin "100") (pinfunction "AVCC_100") (pintype "power_in"))
      (node (ref "L3") (pin "1") (pinfunction "1_1") (pintype "passive"))
    )
    (net (code "111") (name "Net-(IC5-XTAL1)") (class "Default")
      (node (ref "C16") (pin "2") (pinfunction "2_2") (pintype "passive"))
      (node (ref "IC5") (pin "34") (pinfunction "XTAL1_34") (pintype "passive"))
      (node (ref "Q2") (pin "2") (pinfunction "OSC2_2") (pintype "passive"))
    )
    (net (code "112") (name "Net-(IC5-XTAL2)") (class "Default")
      (node (ref "C8") (pin "2") (pinfunction "2_2") (pintype "passive"))
      (node (ref "IC5") (pin "33") (pinfunction "XTAL2_33") (pintype "passive"))
      (node (ref "Q2") (pin "1") (pinfunction "OSC1_1") (pintype "passive"))
    )
    (net (code "113") (name "Net-(IC8-MFP)") (class "Default")
      (node (ref "IC8") (pin "7") (pinfunction "MFP_7") (pintype "open_collector"))
      (node (ref "TP1") (pin "1") (pintype "passive"))
    )
    (net (code "114") (name "Net-(IC8-X1)") (class "Default")
      (node (ref "C19") (pin "1") (pinfunction "1_1") (pintype "passive"))
      (node (ref "IC8") (pin "1") (pinfunction "X1_1") (pintype "input"))
      (node (ref "Q3") (pin "1") (pinfunction "X_1") (pintype "passive"))
    )
    (net (code "115") (name "Net-(IC8-X2)") (class "Default")
      (node (ref "C9") (pin "1") (pinfunction "1_1") (pintype "passive"))
      (node (ref "IC8") (pin "2") (pinfunction "X2_2") (pintype "output"))
      (node (ref "Q3") (pin "4") (pinfunction "X_4") (pintype "passive"))
    )
    (net (code "116") (name "Net-(T1-G)") (class "Default")
      (node (ref "R114") (pin "1") (pinfunction "1_1") (pintype "passive"))
      (node (ref "T1") (pin "1") (pinfunction "G_1") (pintype "passive"))
      (node (ref "T5") (pin "1") (pinfunction "G_1") (pintype "passive"))
    )
    (net (code "117") (name "Net-(T2-G)") (class "Default")
      (node (ref "R158") (pin "2") (pinfunction "2_2") (pintype "passive"))
      (node (ref "R159") (pin "2") (pinfunction "2_2") (pintype "passive"))
      (node (ref "T2") (pin "1") (pinfunction "G_1") (pintype "passive"))
    )
    (net (code "118") (name "P2V5_REF") (class "Default")
      (node (ref "C17") (pin "2") (pinfunction "2_2") (pintype "passive"))
      (node (ref "IC5") (pin "98") (pinfunction "AREF_98") (pintype "input"))
    )
    (net (code "119") (name "P3V3") (class "Default")
      (node (ref "C15") (pin "1") (pinfunction "1_1") (pintype "passive"))
      (node (ref "C30") (pin "1") (pinfunction "1_1") (pintype "passive"))
      (node (ref "C6") (pin "2") (pinfunction "2_2") (pintype "passive"))
      (node (ref "CON2") (pin "23") (pinfunction "23_23") (pintype "passive"))
      (node (ref "CON2") (pin "25") (pinfunction "25_25") (pintype "passive"))
      (node (ref "IC6") (pin "14") (pinfunction "VIO/RFU_14") (pintype "power_in"))
      (node (ref "IC6") (pin "2") (pinfunction "VCC_2") (pintype "power_in"))
      (node (ref "IC7") (pin "8") (pinfunction "VCC_8") (pintype "power_in"))
      (node (ref "IC8") (pin "8") (pinfunction "VCC_8") (pintype "power_in"))
      (node (ref "J1") (pin "4") (pinfunction "4_4") (pintype "passive"))
      (node (ref "R165") (pin "1") (pinfunction "1_1") (pintype "passive"))
      (node (ref "R168") (pin "1") (pinfunction "1_1") (pintype "passive"))
      (node (ref "R2") (pin "2") (pinfunction "2_2") (pintype "passive"))
      (node (ref "R23") (pin "1") (pinfunction "1_1") (pintype "passive"))
      (node (ref "R24") (pin "1") (pinfunction "1_1") (pintype "passive"))
      (node (ref "R26") (pin "1") (pinfunction "1_1") (pintype "passive"))
      (node (ref "R3") (pin "1") (pinfunction "1_1") (pintype "passive"))
      (node (ref "R84") (pin "1") (pinfunction "1_1") (pintype "passive"))
      (node (ref "R85") (pin "1") (pinfunction "1_1") (pintype "passive"))
      (node (ref "R89") (pin "1") (pinfunction "1_1") (pintype "passive"))
      (node (ref "T1") (pin "2") (pinfunction "S_2") (pintype "passive"))
    )
    (net (code "120") (name "P5V0") (class "Default")
      (node (ref "CON2") (pin "22") (pinfunction "22_22") (pintype "passive"))
    )
    (net (code "121") (name "P8V0") (class "Default")
      (node (ref "R114") (pin "2") (pinfunction "2_2") (pintype "passive"))
      (node (ref "R158") (pin "1") (pinfunction "1_1") (pintype "passive"))
    )
    (net (code "122") (name "VCC_UPC") (class "Default")
      (node (ref "C124") (pin "2") (pinfunction "2_2") (pintype "passive"))
      (node (ref "C125") (pin "2") (pinfunction "2_2") (pintype "passive"))
      (node (ref "C126") (pin "2") (pinfunction "2_2") (pintype "passive"))
      (node (ref "C18") (pin "2") (pinfunction "2_2") (pintype "passive"))
      (node (ref "C25") (pin "2") (pinfunction "2_2") (pintype "passive"))
      (node (ref "C38") (pin "2") (pinfunction "2_2") (pintype "passive"))
      (node (ref "CON1") (pin "2") (pinfunction "VCC_2") (pintype "passive"))
      (node (ref "D10") (pin "3") (pinfunction "C_3") (pintype "passive"))
      (node (ref "IC5") (pin "10") (pinfunction "VCC_10") (pintype "power_in"))
      (node (ref "IC5") (pin "31") (pinfunction "VCC_31") (pintype "power_in"))
      (node (ref "IC5") (pin "61") (pinfunction "VCC_61") (pintype "power_in"))
      (node (ref "IC5") (pin "80") (pinfunction "VCC_80") (pintype "power_in"))
      (node (ref "JP1") (pin "4") (pinfunction "4_4") (pintype "passive"))
      (node (ref "L3") (pin "2") (pinfunction "2_2") (pintype "passive"))
      (node (ref "R1") (pin "1") (pinfunction "1_1") (pintype "passive"))
      (node (ref "R113") (pin "2") (pinfunction "2_2") (pintype "passive"))
      (node (ref "R12") (pin "2") (pinfunction "2_2") (pintype "passive"))
      (node (ref "R157") (pin "2") (pinfunction "2_2") (pintype "passive"))
      (node (ref "T1") (pin "3") (pinfunction "D_3") (pintype "passive"))
      (node (ref "T5") (pin "2") (pinfunction "S_2") (pintype "passive"))
    )
    (net (code "123") (name "unconnected-(IC6-NC-Pad13)") (class "Default")
      (node (ref "IC6") (pin "13") (pinfunction "NC_13") (pintype "passive"))
    )
    (net (code "124") (name "unconnected-(IC6-RFU-Pad6)") (class "Default")
      (node (ref "IC6") (pin "6") (pinfunction "RFU_6") (pintype "passive"))
    )
    (net (code "125") (name "unconnected-(IC6-~{HOLD}{slash}IO3-Pad1)") (class "Default")
      (node (ref "IC6") (pin "1") (pinfunction "~{HOLD}/IO3_1") (pintype "bidirectional"))
    )
    (net (code "126") (name "unconnected-(IC6-~{RESET}{slash}RFU-Pad3)") (class "Default")
      (node (ref "IC6") (pin "3") (pinfunction "~{RESET}/RFU_3") (pintype "input"))
    )
    (net (code "127") (name "unconnected-(IC6-~{WP}{slash}IO2-Pad9)") (class "Default")
      (node (ref "IC6") (pin "9") (pinfunction "~{WP}/IO2_9") (pintype "bidirectional"))
    )
    (net (code "128") (name "unconnected-(IC7-~{HOLD}{slash}DQ3-Pad7)") (class "Default")
      (node (ref "IC7") (pin "7") (pinfunction "~{HOLD}/DQ3_7") (pintype "bidirectional"))
    )
    (net (code "129") (name "unconnected-(IC7-~{W}{slash}Vpp{slash}DQ2-Pad3)") (class "Default")
      (node (ref "IC7") (pin "3") (pinfunction "~{W}/Vpp/DQ2_3") (pintype "bidirectional"))
    )
    (net (code "130") (name "unconnected-(JP1-Pad7)") (class "Default")
      (node (ref "JP1") (pin "7") (pinfunction "7_7") (pintype "passive"))
    )
    (net (code "131") (name "unconnected-(JP1-Pad8)") (class "Default")
      (node (ref "JP1") (pin "8") (pinfunction "8_8") (pintype "passive"))
    )
  )
)
